# basic-inline-turbidimeter_main_board_v2_.net
KiCad netlist of a schematic drawn in EAGLE
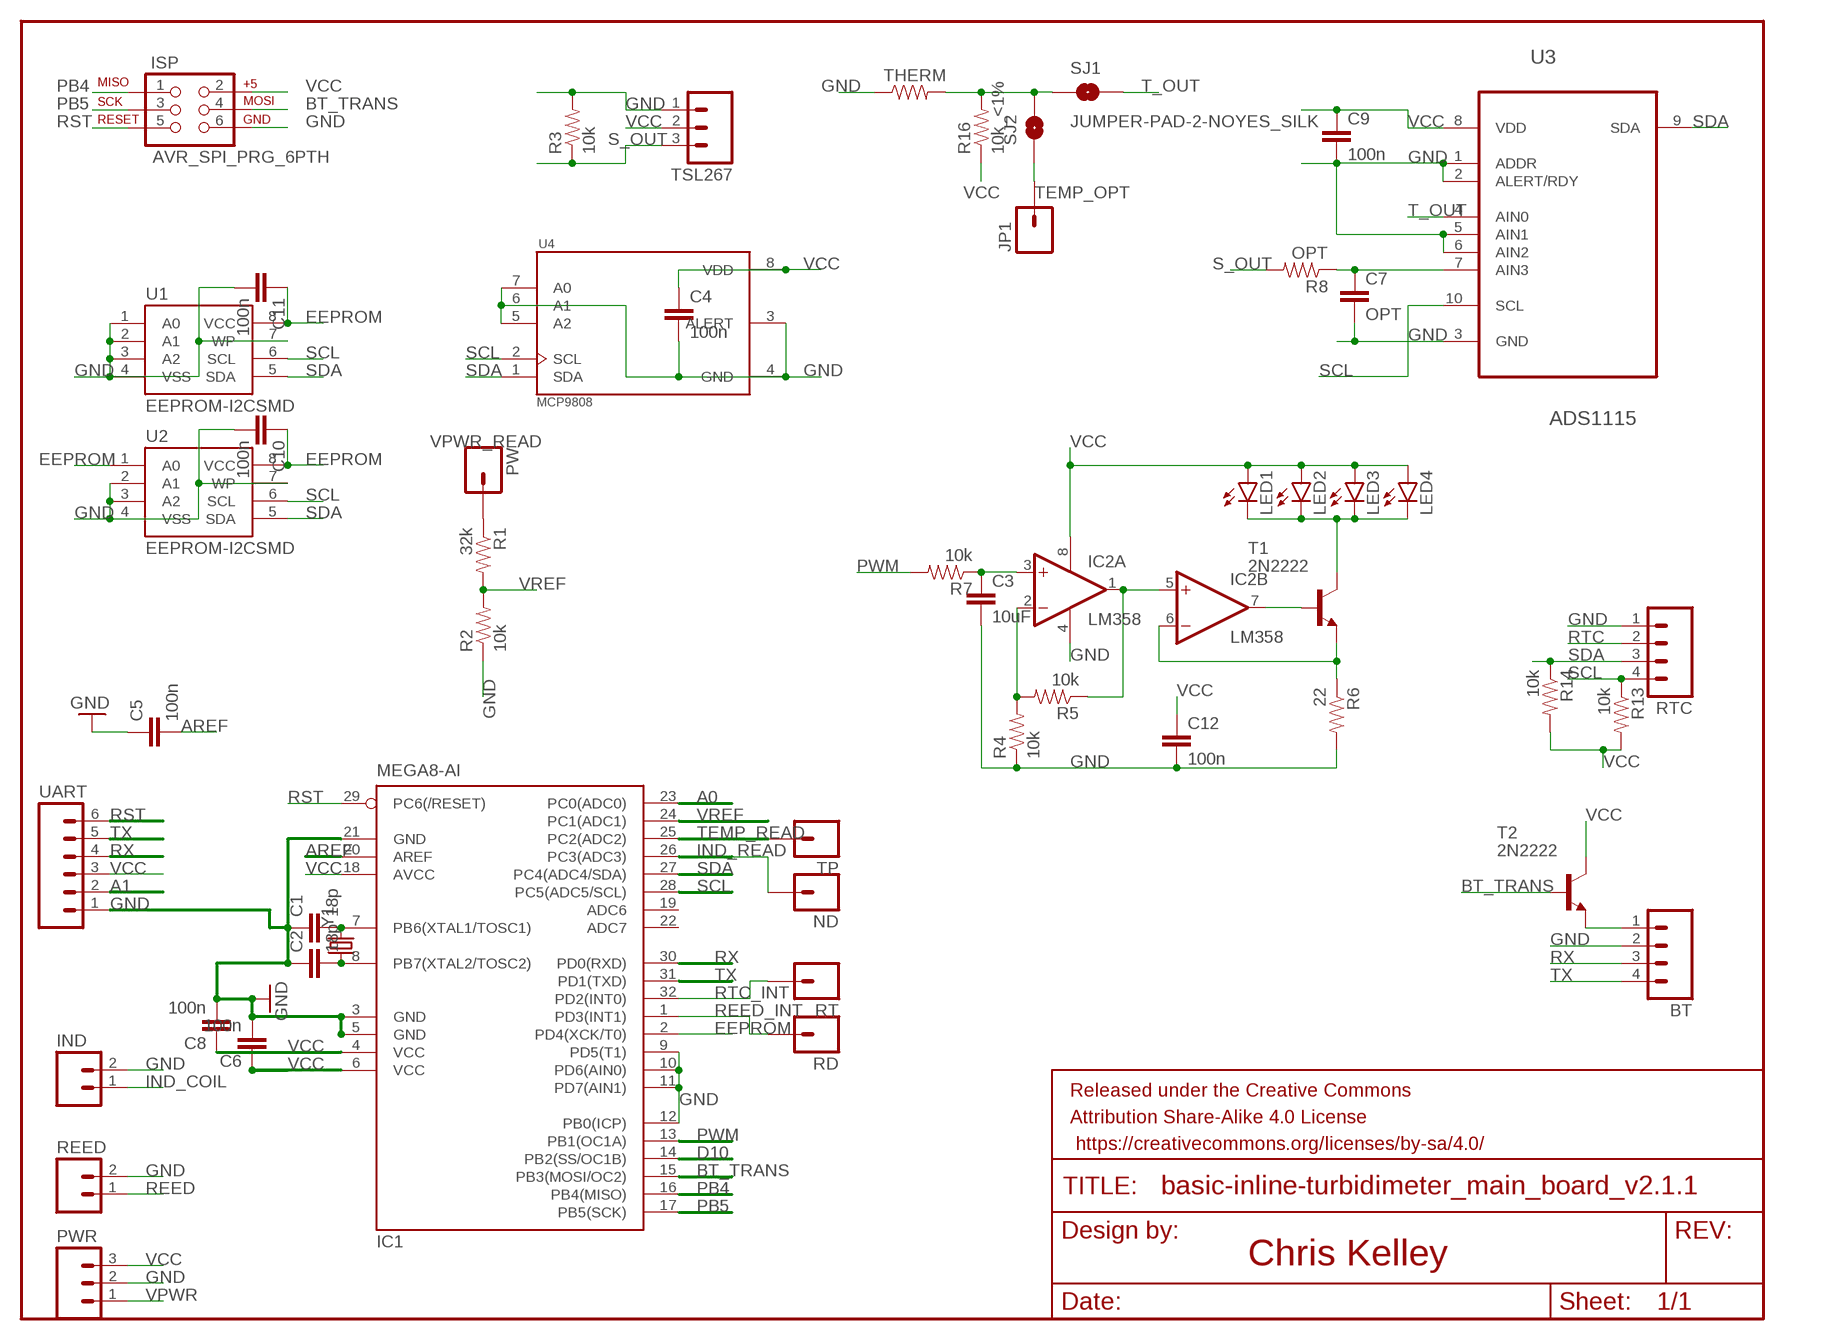
[diagram p0: schematic, sheet 1]

(export (version "E")
  (design (tool "Eeschema 10.0.6"))
  (components
    (comp (ref "BT")
      (value "M04PTH")
      (footprint "eagle-import:1X04")
      (libsource (lib "eagle-import") (part "M04PTH"))
    )
    (comp (ref "C1")
      (value "18p")
      (footprint "eagle-import:0603-CAP")
      (libsource (lib "eagle-import") (part "CAP0603-CAP"))
    )
    (comp (ref "C2")
      (value "18p")
      (footprint "eagle-import:0603-CAP")
      (libsource (lib "eagle-import") (part "CAP0603-CAP"))
    )
    (comp (ref "C3")
      (value "10uF")
      (footprint "eagle-import:0603-CAP")
      (libsource (lib "eagle-import") (part "CAP0603-CAP"))
    )
    (comp (ref "C4")
      (value "100n")
      (footprint "eagle-import:0603-CAP")
      (libsource (lib "eagle-import") (part "CAP0603-CAP"))
    )
    (comp (ref "C5")
      (value "100n")
      (footprint "eagle-import:0603-CAP")
      (libsource (lib "eagle-import") (part "CAP0603-CAP"))
    )
    (comp (ref "C6")
      (value "100n")
      (footprint "eagle-import:0603-CAP")
      (libsource (lib "eagle-import") (part "CAP0603-CAP"))
    )
    (comp (ref "C7")
      (value "OPT")
      (footprint "eagle-import:0603-CAP")
      (libsource (lib "eagle-import") (part "CAP0603-CAP"))
    )
    (comp (ref "C8")
      (value "100n")
      (footprint "eagle-import:0603-CAP")
      (libsource (lib "eagle-import") (part "CAP0603-CAP"))
    )
    (comp (ref "C9")
      (value "100n")
      (footprint "eagle-import:0603-CAP")
      (libsource (lib "eagle-import") (part "CAP0603-CAP"))
    )
    (comp (ref "C10")
      (value "100n")
      (footprint "eagle-import:0603-CAP")
      (libsource (lib "eagle-import") (part "CAP0603-CAP"))
    )
    (comp (ref "C11")
      (value "100n")
      (footprint "eagle-import:0603-CAP")
      (libsource (lib "eagle-import") (part "CAP0603-CAP"))
    )
    (comp (ref "C12")
      (value "100n")
      (footprint "eagle-import:0603-CAP")
      (libsource (lib "eagle-import") (part "CAP0603-CAP"))
    )
    (comp (ref "FRAME1")
      (value "FRAME-LETTER")
      (footprint "eagle-import:CREATIVE_COMMONS")
      (libsource (lib "eagle-import") (part "FRAME-LETTER"))
    )
    (comp (ref "IC1")
      (value "MEGA8-AI")
      (footprint "eagle-import:TQFP32-08")
      (fields (field (name "MPN") "ATMEGA8-16AU"))
      (libsource (lib "eagle-import") (part "MEGA8-AI"))
    )
    (comp (ref "IC2")
      (value "LM358")
      (footprint "eagle-import:SO08")
      (libsource (lib "eagle-import") (part "LM358D"))
    )
    (comp (ref "IND")
      (value "M02PTH")
      (footprint "eagle-import:1X02")
      (libsource (lib "eagle-import") (part "M02PTH"))
    )
    (comp (ref "ISP")
      (value "AVR_SPI_PRG_6PTH")
      (footprint "eagle-import:2X3")
      (libsource (lib "eagle-import") (part "AVR_SPI_PRG_6PTH"))
    )
    (comp (ref "JP1")
      (value "M01PTH")
      (footprint "eagle-import:1X01")
      (libsource (lib "eagle-import") (part "M01PTH"))
    )
    (comp (ref "LED1")
      (value "LED5MM")
      (footprint "eagle-import:LED5MM")
      (libsource (lib "eagle-import") (part "LED5MM"))
    )
    (comp (ref "LED2")
      (value "LED5MM")
      (footprint "eagle-import:LED5MM")
      (libsource (lib "eagle-import") (part "LED5MM"))
    )
    (comp (ref "LED3")
      (value "LED5MM")
      (footprint "eagle-import:LED5MM")
      (libsource (lib "eagle-import") (part "LED5MM"))
    )
    (comp (ref "LED4")
      (value "LED5MM")
      (footprint "eagle-import:LED5MM")
      (libsource (lib "eagle-import") (part "LED5MM"))
    )
    (comp (ref "ND")
      (value "M01PTH")
      (footprint "eagle-import:1X01")
      (libsource (lib "eagle-import") (part "M01PTH"))
    )
    (comp (ref "PW")
      (value "M01PTH")
      (footprint "eagle-import:1X01")
      (libsource (lib "eagle-import") (part "M01PTH"))
    )
    (comp (ref "PWR")
      (value "M03PTH")
      (footprint "eagle-import:1X03")
      (libsource (lib "eagle-import") (part "M03PTH"))
    )
    (comp (ref "R1")
      (value "32k")
      (footprint "eagle-import:0603-RES")
      (libsource (lib "eagle-import") (part "RESISTOR0603"))
    )
    (comp (ref "R2")
      (value "10k")
      (footprint "eagle-import:0603-RES")
      (libsource (lib "eagle-import") (part "RESISTOR0603"))
    )
    (comp (ref "R3")
      (value "10k")
      (footprint "eagle-import:0603-RES")
      (libsource (lib "eagle-import") (part "RESISTOR0603"))
    )
    (comp (ref "R4")
      (value "10k")
      (footprint "eagle-import:0603-RES")
      (libsource (lib "eagle-import") (part "RESISTOR0603"))
    )
    (comp (ref "R5")
      (value "10k")
      (footprint "eagle-import:0603-RES")
      (libsource (lib "eagle-import") (part "RESISTOR0603"))
    )
    (comp (ref "R6")
      (value "22")
      (footprint "eagle-import:0603-RES")
      (libsource (lib "eagle-import") (part "RESISTOR0603"))
    )
    (comp (ref "R7")
      (value "10k")
      (footprint "eagle-import:0603-RES")
      (libsource (lib "eagle-import") (part "RESISTOR0603"))
    )
    (comp (ref "R8")
      (value "OPT")
      (footprint "eagle-import:0603-RES")
      (libsource (lib "eagle-import") (part "RESISTOR0603"))
    )
    (comp (ref "R13")
      (value "10k")
      (footprint "eagle-import:0603-RES")
      (libsource (lib "eagle-import") (part "RESISTOR0603"))
    )
    (comp (ref "R14")
      (value "10k")
      (footprint "eagle-import:0603-RES")
      (libsource (lib "eagle-import") (part "RESISTOR0603"))
    )
    (comp (ref "R16")
      (value "10k_<1%")
      (footprint "eagle-import:0603-RES")
      (libsource (lib "eagle-import") (part "RESISTOR0603-RES"))
    )
    (comp (ref "RD")
      (value "M01PTH")
      (footprint "eagle-import:1X01")
      (libsource (lib "eagle-import") (part "M01PTH"))
    )
    (comp (ref "REED")
      (value "M02PTH")
      (footprint "eagle-import:1X02")
      (libsource (lib "eagle-import") (part "M02PTH"))
    )
    (comp (ref "RT")
      (value "M01PTH")
      (footprint "eagle-import:1X01")
      (libsource (lib "eagle-import") (part "M01PTH"))
    )
    (comp (ref "RTC")
      (value "M04PTH")
      (footprint "eagle-import:1X04")
      (libsource (lib "eagle-import") (part "M04PTH"))
    )
    (comp (ref "SJ1")
      (value "JUMPER-PAD-2-NOYES_SILK")
      (footprint "eagle-import:PAD-JUMPER-2-NO_YES_SILK")
      (libsource (lib "eagle-import") (part "JUMPER-PAD-2-NOYES_SILK"))
    )
    (comp (ref "SJ2")
      (value "JUMPER-PAD-2-NOYES_SILK")
      (footprint "eagle-import:PAD-JUMPER-2-NO_YES_SILK")
      (libsource (lib "eagle-import") (part "JUMPER-PAD-2-NOYES_SILK"))
    )
    (comp (ref "T1")
      (value "2N2222")
      (footprint "eagle-import:TO92-EBC-OVAL")
      (libsource (lib "eagle-import") (part "2N2222"))
    )
    (comp (ref "T2")
      (value "2N2222")
      (footprint "eagle-import:TO92-EBC-OVAL")
      (libsource (lib "eagle-import") (part "2N2222"))
    )
    (comp (ref "THERM")
      (value "RESISTOR0603-RES")
      (footprint "eagle-import:0603-RES")
      (libsource (lib "eagle-import") (part "RESISTOR0603-RES"))
    )
    (comp (ref "TP")
      (value "M01PTH")
      (footprint "eagle-import:1X01")
      (libsource (lib "eagle-import") (part "M01PTH"))
    )
    (comp (ref "TSL267")
      (value "M03PTH")
      (footprint "eagle-import:1X03")
      (libsource (lib "eagle-import") (part "M03PTH"))
    )
    (comp (ref "U1")
      (value "EEPROM-I2CSMD")
      (footprint "eagle-import:SO08")
      (libsource (lib "eagle-import") (part "EEPROM-I2CSMD"))
    )
    (comp (ref "U2")
      (value "EEPROM-I2CSMD")
      (footprint "eagle-import:SO08")
      (libsource (lib "eagle-import") (part "EEPROM-I2CSMD"))
    )
    (comp (ref "U3")
      (value "ADS1115")
      (footprint "eagle-import:SOP50P490X110-10N")
      (fields (field (name "MF") "Texas Instruments") (field (name "MP") "ADS1115IDGST"))
      (libsource (lib "eagle-import") (part "ADS1115IDGST"))
    )
    (comp (ref "U4")
      (value "MCP9808")
      (footprint "eagle-import:SOP65P490X110-8N")
      (fields (field (name "MF") "Microchip") (field (name "MP") "MCP9808-E/MS"))
      (libsource (lib "eagle-import") (part "MCP9808-E/MS"))
    )
    (comp (ref "UART")
      (value "M06SILK_FEMALE_PTH")
      (footprint "eagle-import:1X06")
      (libsource (lib "eagle-import") (part "M06SILK_FEMALE_PTH"))
    )
    (comp (ref "Y1")
      (value "CRYSTAL5X3")
      (footprint "eagle-import:CRYSTAL-SMD-5X3")
      (libsource (lib "eagle-import") (part "CRYSTAL5X3"))
    )
  )
  (nets
    (net (code "1") (name "/A0") (class "Default")
      (node (ref "IC1") (pin "23") (pinfunction "PC0(ADC0)_23") (pintype "bidirectional"))
    )
    (net (code "2") (name "/A1") (class "Default")
      (node (ref "UART") (pin "2") (pinfunction "2_2") (pintype "passive"))
    )
    (net (code "3") (name "/AREF") (class "Default")
      (node (ref "C5") (pin "2") (pinfunction "2_2") (pintype "passive"))
      (node (ref "IC1") (pin "20") (pinfunction "AREF_20") (pintype "passive"))
    )
    (net (code "4") (name "/BT_TRANS") (class "Default")
      (node (ref "IC1") (pin "15") (pinfunction "PB3(MOSI/OC2)_15") (pintype "bidirectional"))
      (node (ref "ISP") (pin "4") (pinfunction "4_4") (pintype "passive"))
      (node (ref "T2") (pin "B") (pinfunction "B_B") (pintype "passive"))
    )
    (net (code "5") (name "/D10") (class "Default")
      (node (ref "IC1") (pin "14") (pinfunction "PB2(SS/OC1B)_14") (pintype "bidirectional"))
    )
    (net (code "6") (name "/EEPROM") (class "Default")
      (node (ref "C10") (pin "1") (pinfunction "1_1") (pintype "passive"))
      (node (ref "C11") (pin "1") (pinfunction "1_1") (pintype "passive"))
      (node (ref "IC1") (pin "2") (pinfunction "PD4(XCK/T0)_2") (pintype "bidirectional"))
      (node (ref "U1") (pin "8") (pinfunction "VCC_8") (pintype "power_in"))
      (node (ref "U2") (pin "1") (pinfunction "A0_1") (pintype "bidirectional"))
      (node (ref "U2") (pin "8") (pinfunction "VCC_8") (pintype "power_in"))
    )
    (net (code "7") (name "/IND_COIL") (class "Default")
      (node (ref "IND") (pin "1") (pinfunction "1_1") (pintype "passive"))
    )
    (net (code "8") (name "/IND_READ") (class "Default")
      (node (ref "IC1") (pin "26") (pinfunction "PC3(ADC3)_26") (pintype "bidirectional"))
      (node (ref "ND") (pin "1") (pinfunction "1_1") (pintype "passive"))
    )
    (net (code "9") (name "/PB4") (class "Default")
      (node (ref "IC1") (pin "16") (pinfunction "PB4(MISO)_16") (pintype "bidirectional"))
      (node (ref "ISP") (pin "1") (pinfunction "1_1") (pintype "passive"))
    )
    (net (code "10") (name "/PB5") (class "Default")
      (node (ref "IC1") (pin "17") (pinfunction "PB5(SCK)_17") (pintype "bidirectional"))
      (node (ref "ISP") (pin "3") (pinfunction "3_3") (pintype "passive"))
    )
    (net (code "11") (name "/PWM") (class "Default")
      (node (ref "IC1") (pin "13") (pinfunction "PB1(OC1A)_13") (pintype "bidirectional"))
      (node (ref "R7") (pin "2") (pinfunction "2_2") (pintype "passive"))
    )
    (net (code "12") (name "/REED") (class "Default")
      (node (ref "REED") (pin "1") (pinfunction "1_1") (pintype "passive"))
    )
    (net (code "13") (name "/REED_INT") (class "Default")
      (node (ref "IC1") (pin "1") (pinfunction "PD3(INT1)_1") (pintype "bidirectional"))
      (node (ref "RD") (pin "1") (pinfunction "1_1") (pintype "passive"))
    )
    (net (code "14") (name "/RST") (class "Default")
      (node (ref "IC1") (pin "29") (pinfunction "PC6(/RESET)_29") (pintype "bidirectional"))
      (node (ref "ISP") (pin "5") (pinfunction "5_5") (pintype "passive"))
      (node (ref "UART") (pin "6") (pinfunction "6_6") (pintype "passive"))
    )
    (net (code "15") (name "/RTC") (class "Default")
      (node (ref "RTC") (pin "2") (pinfunction "2_2") (pintype "passive"))
    )
    (net (code "16") (name "/RTC_INT") (class "Default")
      (node (ref "IC1") (pin "32") (pinfunction "PD2(INT0)_32") (pintype "bidirectional"))
      (node (ref "RT") (pin "1") (pinfunction "1_1") (pintype "passive"))
    )
    (net (code "17") (name "/RX") (class "Default")
      (node (ref "BT") (pin "3") (pinfunction "3_3") (pintype "passive"))
      (node (ref "IC1") (pin "30") (pinfunction "PD0(RXD)_30") (pintype "bidirectional"))
      (node (ref "UART") (pin "4") (pinfunction "4_4") (pintype "passive"))
    )
    (net (code "18") (name "/SCL") (class "Default")
      (node (ref "IC1") (pin "28") (pinfunction "PC5(ADC5/SCL)_28") (pintype "bidirectional"))
      (node (ref "R13") (pin "1") (pinfunction "1_1") (pintype "passive"))
      (node (ref "RTC") (pin "4") (pinfunction "4_4") (pintype "passive"))
      (node (ref "U1") (pin "6") (pinfunction "SCL_6") (pintype "bidirectional"))
      (node (ref "U2") (pin "6") (pinfunction "SCL_6") (pintype "bidirectional"))
      (node (ref "U3") (pin "10") (pinfunction "SCL_10") (pintype "input"))
      (node (ref "U4") (pin "2") (pinfunction "SCL_2") (pintype "input"))
    )
    (net (code "19") (name "/SDA") (class "Default")
      (node (ref "IC1") (pin "27") (pinfunction "PC4(ADC4/SDA)_27") (pintype "bidirectional"))
      (node (ref "R14") (pin "1") (pinfunction "1_1") (pintype "passive"))
      (node (ref "RTC") (pin "3") (pinfunction "3_3") (pintype "passive"))
      (node (ref "U1") (pin "5") (pinfunction "SDA_5") (pintype "bidirectional"))
      (node (ref "U2") (pin "5") (pinfunction "SDA_5") (pintype "bidirectional"))
      (node (ref "U3") (pin "9") (pinfunction "SDA_9") (pintype "bidirectional"))
      (node (ref "U4") (pin "1") (pinfunction "SDA_1") (pintype "bidirectional"))
    )
    (net (code "20") (name "/S_OUT") (class "Default")
      (node (ref "R3") (pin "1") (pinfunction "1_1") (pintype "passive"))
      (node (ref "R8") (pin "2") (pinfunction "2_2") (pintype "passive"))
      (node (ref "TSL267") (pin "3") (pinfunction "3_3") (pintype "passive"))
    )
    (net (code "21") (name "/TEMP_OPT") (class "Default")
      (node (ref "JP1") (pin "1") (pinfunction "1_1") (pintype "passive"))
      (node (ref "SJ2") (pin "1") (pinfunction "1_1") (pintype "passive"))
    )
    (net (code "22") (name "/TEMP_READ") (class "Default")
      (node (ref "IC1") (pin "25") (pinfunction "PC2(ADC2)_25") (pintype "bidirectional"))
      (node (ref "TP") (pin "1") (pinfunction "1_1") (pintype "passive"))
    )
    (net (code "23") (name "/TX") (class "Default")
      (node (ref "BT") (pin "4") (pinfunction "4_4") (pintype "passive"))
      (node (ref "IC1") (pin "31") (pinfunction "PD1(TXD)_31") (pintype "bidirectional"))
      (node (ref "UART") (pin "5") (pinfunction "5_5") (pintype "passive"))
    )
    (net (code "24") (name "/T_OUT") (class "Default")
      (node (ref "SJ1") (pin "2") (pinfunction "2_2") (pintype "passive"))
      (node (ref "U3") (pin "4") (pinfunction "AIN0_4") (pintype "input"))
    )
    (net (code "25") (name "/VCC") (class "Default")
      (node (ref "C12") (pin "1") (pinfunction "1_1") (pintype "passive"))
      (node (ref "C4") (pin "1") (pinfunction "1_1") (pintype "passive"))
      (node (ref "C6") (pin "1") (pinfunction "1_1") (pintype "passive"))
      (node (ref "C8") (pin "1") (pinfunction "1_1") (pintype "passive"))
      (node (ref "C9") (pin "1") (pinfunction "1_1") (pintype "passive"))
      (node (ref "IC1") (pin "18") (pinfunction "AVCC_18") (pintype "power_in"))
      (node (ref "IC1") (pin "4") (pinfunction "VCC_4") (pintype "power_in"))
      (node (ref "IC1") (pin "6") (pinfunction "VCC_6") (pintype "power_in"))
      (node (ref "IC2") (pin "8") (pinfunction "V+_8") (pintype "power_in"))
      (node (ref "ISP") (pin "2") (pinfunction "2_2") (pintype "passive"))
      (node (ref "LED1") (pin "A") (pinfunction "A_A") (pintype "passive"))
      (node (ref "LED2") (pin "A") (pinfunction "A_A") (pintype "passive"))
      (node (ref "LED3") (pin "A") (pinfunction "A_A") (pintype "passive"))
      (node (ref "LED4") (pin "A") (pinfunction "A_A") (pintype "passive"))
      (node (ref "PWR") (pin "3") (pinfunction "3_3") (pintype "passive"))
      (node (ref "R13") (pin "2") (pinfunction "2_2") (pintype "passive"))
      (node (ref "R14") (pin "2") (pinfunction "2_2") (pintype "passive"))
      (node (ref "R16") (pin "1") (pinfunction "1_1") (pintype "passive"))
      (node (ref "T2") (pin "C") (pinfunction "C_C") (pintype "passive"))
      (node (ref "TSL267") (pin "2") (pinfunction "2_2") (pintype "passive"))
      (node (ref "U3") (pin "8") (pinfunction "VDD_8") (pintype "power_in"))
      (node (ref "U4") (pin "8") (pinfunction "VDD_8") (pintype "power_in"))
      (node (ref "UART") (pin "3") (pinfunction "3_3") (pintype "passive"))
    )
    (net (code "26") (name "/VPWR") (class "Default")
      (node (ref "PWR") (pin "1") (pinfunction "1_1") (pintype "passive"))
    )
    (net (code "28") (name "/VREF") (class "Default")
      (node (ref "IC1") (pin "24") (pinfunction "PC1(ADC1)_24") (pintype "bidirectional"))
      (node (ref "R1") (pin "2") (pinfunction "2_2") (pintype "passive"))
      (node (ref "R2") (pin "2") (pinfunction "2_2") (pintype "passive"))
    )
    (net (code "29") (name "GND") (class "Default")
      (node (ref "BT") (pin "2") (pinfunction "2_2") (pintype "passive"))
      (node (ref "C1") (pin "1") (pinfunction "1_1") (pintype "passive"))
      (node (ref "C10") (pin "2") (pinfunction "2_2") (pintype "passive"))
      (node (ref "C11") (pin "2") (pinfunction "2_2") (pintype "passive"))
      (node (ref "C12") (pin "2") (pinfunction "2_2") (pintype "passive"))
      (node (ref "C2") (pin "1") (pinfunction "1_1") (pintype "passive"))
      (node (ref "C3") (pin "2") (pinfunction "2_2") (pintype "passive"))
      (node (ref "C4") (pin "2") (pinfunction "2_2") (pintype "passive"))
      (node (ref "C5") (pin "1") (pinfunction "1_1") (pintype "passive"))
      (node (ref "C6") (pin "2") (pinfunction "2_2") (pintype "passive"))
      (node (ref "C7") (pin "2") (pinfunction "2_2") (pintype "passive"))
      (node (ref "C8") (pin "2") (pinfunction "2_2") (pintype "passive"))
      (node (ref "C9") (pin "2") (pinfunction "2_2") (pintype "passive"))
      (node (ref "IC1") (pin "10") (pinfunction "PD6(AIN0)_10") (pintype "bidirectional"))
      (node (ref "IC1") (pin "11") (pinfunction "PD7(AIN1)_11") (pintype "bidirectional"))
      (node (ref "IC1") (pin "12") (pinfunction "PB0(ICP)_12") (pintype "bidirectional"))
      (node (ref "IC1") (pin "21") (pinfunction "GND_21") (pintype "power_in"))
      (node (ref "IC1") (pin "3") (pinfunction "GND_3") (pintype "power_in"))
      (node (ref "IC1") (pin "5") (pinfunction "GND_5") (pintype "power_in"))
      (node (ref "IC1") (pin "9") (pinfunction "PD5(T1)_9") (pintype "bidirectional"))
      (node (ref "IC2") (pin "4") (pinfunction "V-_4") (pintype "power_in"))
      (node (ref "IND") (pin "2") (pinfunction "2_2") (pintype "passive"))
      (node (ref "ISP") (pin "6") (pinfunction "6_6") (pintype "passive"))
      (node (ref "PWR") (pin "2") (pinfunction "2_2") (pintype "passive"))
      (node (ref "R2") (pin "1") (pinfunction "1_1") (pintype "passive"))
      (node (ref "R3") (pin "2") (pinfunction "2_2") (pintype "passive"))
      (node (ref "R4") (pin "1") (pinfunction "1_1") (pintype "passive"))
      (node (ref "R6") (pin "2") (pinfunction "2_2") (pintype "passive"))
      (node (ref "REED") (pin "2") (pinfunction "2_2") (pintype "passive"))
      (node (ref "RTC") (pin "1") (pinfunction "1_1") (pintype "passive"))
      (node (ref "THERM") (pin "1") (pinfunction "1_1") (pintype "passive"))
      (node (ref "TSL267") (pin "1") (pinfunction "1_1") (pintype "passive"))
      (node (ref "U1") (pin "1") (pinfunction "A0_1") (pintype "bidirectional"))
      (node (ref "U1") (pin "2") (pinfunction "A1_2") (pintype "bidirectional"))
      (node (ref "U1") (pin "3") (pinfunction "A2_3") (pintype "bidirectional"))
      (node (ref "U1") (pin "4") (pinfunction "VSS_4") (pintype "power_in"))
      (node (ref "U1") (pin "7") (pinfunction "WP_7") (pintype "bidirectional"))
      (node (ref "U2") (pin "2") (pinfunction "A1_2") (pintype "bidirectional"))
      (node (ref "U2") (pin "3") (pinfunction "A2_3") (pintype "bidirectional"))
      (node (ref "U2") (pin "4") (pinfunction "VSS_4") (pintype "power_in"))
      (node (ref "U2") (pin "7") (pinfunction "WP_7") (pintype "bidirectional"))
      (node (ref "U3") (pin "1") (pinfunction "ADDR_1") (pintype "input"))
      (node (ref "U3") (pin "2") (pinfunction "ALERT/RDY_2") (pintype "input"))
      (node (ref "U3") (pin "3") (pinfunction "GND_3") (pintype "passive"))
      (node (ref "U3") (pin "5") (pinfunction "AIN1_5") (pintype "input"))
      (node (ref "U3") (pin "6") (pinfunction "AIN2_6") (pintype "input"))
      (node (ref "U4") (pin "3") (pinfunction "ALERT_3") (pintype "output"))
      (node (ref "U4") (pin "4") (pinfunction "GND_4") (pintype "power_in"))
      (node (ref "U4") (pin "5") (pinfunction "A2_5") (pintype "input"))
      (node (ref "U4") (pin "6") (pinfunction "A1_6") (pintype "input"))
      (node (ref "U4") (pin "7") (pinfunction "A0_7") (pintype "input"))
      (node (ref "UART") (pin "1") (pinfunction "1_1") (pintype "passive"))
    )
    (net (code "30") (name "Net-(BT-Pad1)") (class "Default")
      (node (ref "BT") (pin "1") (pinfunction "1_1") (pintype "passive"))
      (node (ref "T2") (pin "E") (pinfunction "E_E") (pintype "passive"))
    )
    (net (code "31") (name "Net-(IC1-PB6(XTAL1{slash}TOSC1))") (class "Default")
      (node (ref "C1") (pin "2") (pinfunction "2_2") (pintype "passive"))
      (node (ref "IC1") (pin "7") (pinfunction "PB6(XTAL1/TOSC1)_7") (pintype "bidirectional"))
      (node (ref "Y1") (pin "3") (pinfunction "2_3") (pintype "passive"))
    )
    (net (code "32") (name "Net-(IC1-PB7(XTAL2{slash}TOSC2))") (class "Default")
      (node (ref "C2") (pin "2") (pinfunction "2_2") (pintype "passive"))
      (node (ref "IC1") (pin "8") (pinfunction "PB7(XTAL2/TOSC2)_8") (pintype "bidirectional"))
      (node (ref "Y1") (pin "1") (pinfunction "1_1") (pintype "passive"))
    )
    (net (code "33") (name "Net-(IC2A-+IN)") (class "Default")
      (node (ref "C3") (pin "1") (pinfunction "1_1") (pintype "passive"))
      (node (ref "IC2") (pin "3") (pinfunction "+IN_3") (pintype "input"))
      (node (ref "R7") (pin "1") (pinfunction "1_1") (pintype "passive"))
    )
    (net (code "34") (name "Net-(IC2A--IN)") (class "Default")
      (node (ref "IC2") (pin "2") (pinfunction "-IN_2") (pintype "input"))
      (node (ref "R4") (pin "2") (pinfunction "2_2") (pintype "passive"))
      (node (ref "R5") (pin "2") (pinfunction "2_2") (pintype "passive"))
    )
    (net (code "35") (name "Net-(IC2A-OUT)") (class "Default")
      (node (ref "IC2") (pin "1") (pinfunction "OUT_1") (pintype "output"))
      (node (ref "IC2") (pin "5") (pinfunction "+IN_5") (pintype "input"))
      (node (ref "R5") (pin "1") (pinfunction "1_1") (pintype "passive"))
    )
    (net (code "36") (name "Net-(IC2B--IN)") (class "Default")
      (node (ref "IC2") (pin "6") (pinfunction "-IN_6") (pintype "input"))
      (node (ref "R6") (pin "1") (pinfunction "1_1") (pintype "passive"))
      (node (ref "T1") (pin "E") (pinfunction "E_E") (pintype "passive"))
    )
    (net (code "37") (name "Net-(IC2B-OUT)") (class "Default")
      (node (ref "IC2") (pin "7") (pinfunction "OUT_7") (pintype "output"))
      (node (ref "T1") (pin "B") (pinfunction "B_B") (pintype "passive"))
    )
    (net (code "38") (name "Net-(LED1-C)") (class "Default")
      (node (ref "LED1") (pin "K") (pinfunction "C_K") (pintype "passive"))
      (node (ref "LED2") (pin "K") (pinfunction "C_K") (pintype "passive"))
      (node (ref "LED3") (pin "K") (pinfunction "C_K") (pintype "passive"))
      (node (ref "LED4") (pin "K") (pinfunction "C_K") (pintype "passive"))
      (node (ref "T1") (pin "C") (pinfunction "C_C") (pintype "passive"))
    )
    (net (code "39") (name "Net-(PW-Pad1)") (class "Default")
      (node (ref "PW") (pin "1") (pinfunction "1_1") (pintype "passive"))
      (node (ref "R1") (pin "1") (pinfunction "1_1") (pintype "passive"))
    )
    (net (code "40") (name "Net-(R16-Pad2)") (class "Default")
      (node (ref "R16") (pin "2") (pinfunction "2_2") (pintype "passive"))
      (node (ref "SJ1") (pin "1") (pinfunction "1_1") (pintype "passive"))
      (node (ref "SJ2") (pin "2") (pinfunction "2_2") (pintype "passive"))
      (node (ref "THERM") (pin "2") (pinfunction "2_2") (pintype "passive"))
    )
    (net (code "41") (name "Net-(U3-AIN3)") (class "Default")
      (node (ref "C7") (pin "1") (pinfunction "1_1") (pintype "passive"))
      (node (ref "R8") (pin "1") (pinfunction "1_1") (pintype "passive"))
      (node (ref "U3") (pin "7") (pinfunction "AIN3_7") (pintype "input"))
    )
    (net (code "42") (name "unconnected-(IC1-ADC6-Pad19)") (class "Default")
      (node (ref "IC1") (pin "19") (pinfunction "ADC6_19") (pintype "bidirectional"))
    )
    (net (code "43") (name "unconnected-(IC1-ADC7-Pad22)") (class "Default")
      (node (ref "IC1") (pin "22") (pinfunction "ADC7_22") (pintype "bidirectional"))
    )
  )
)
